# arduino_board_rev_1_4.net
KiCad netlist of a schematic drawn in EAGLE
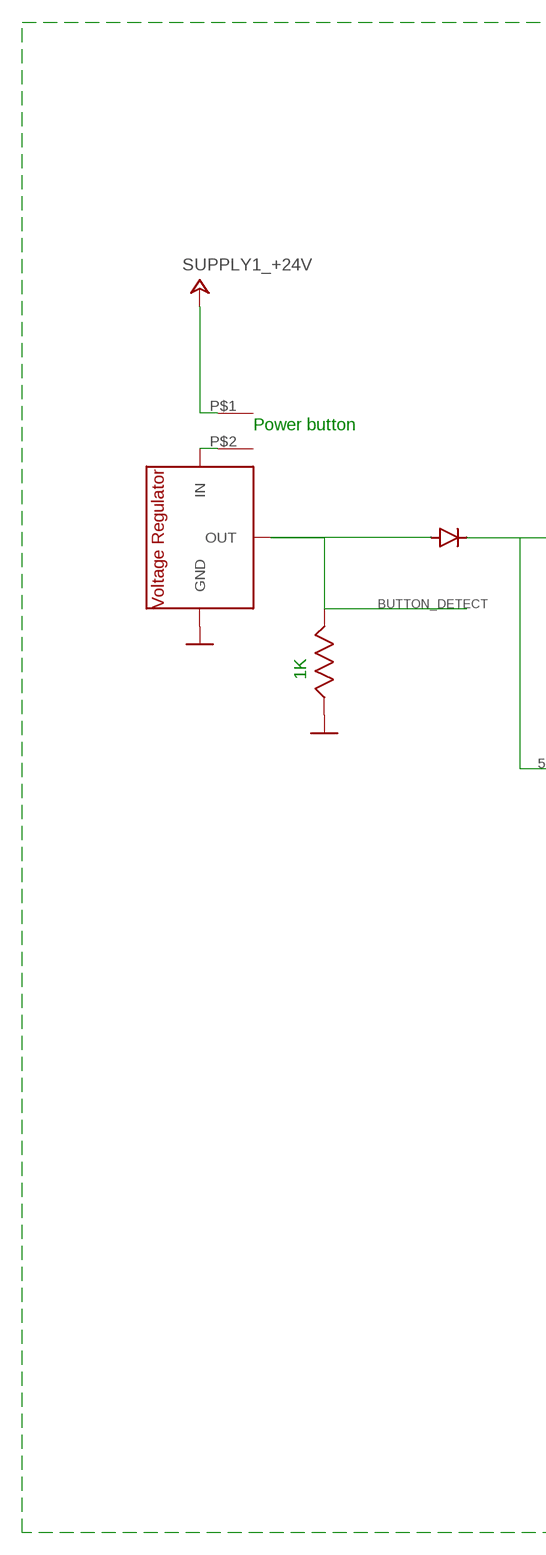
[diagram p0: schematic, sheet 1, part 1 of 2]
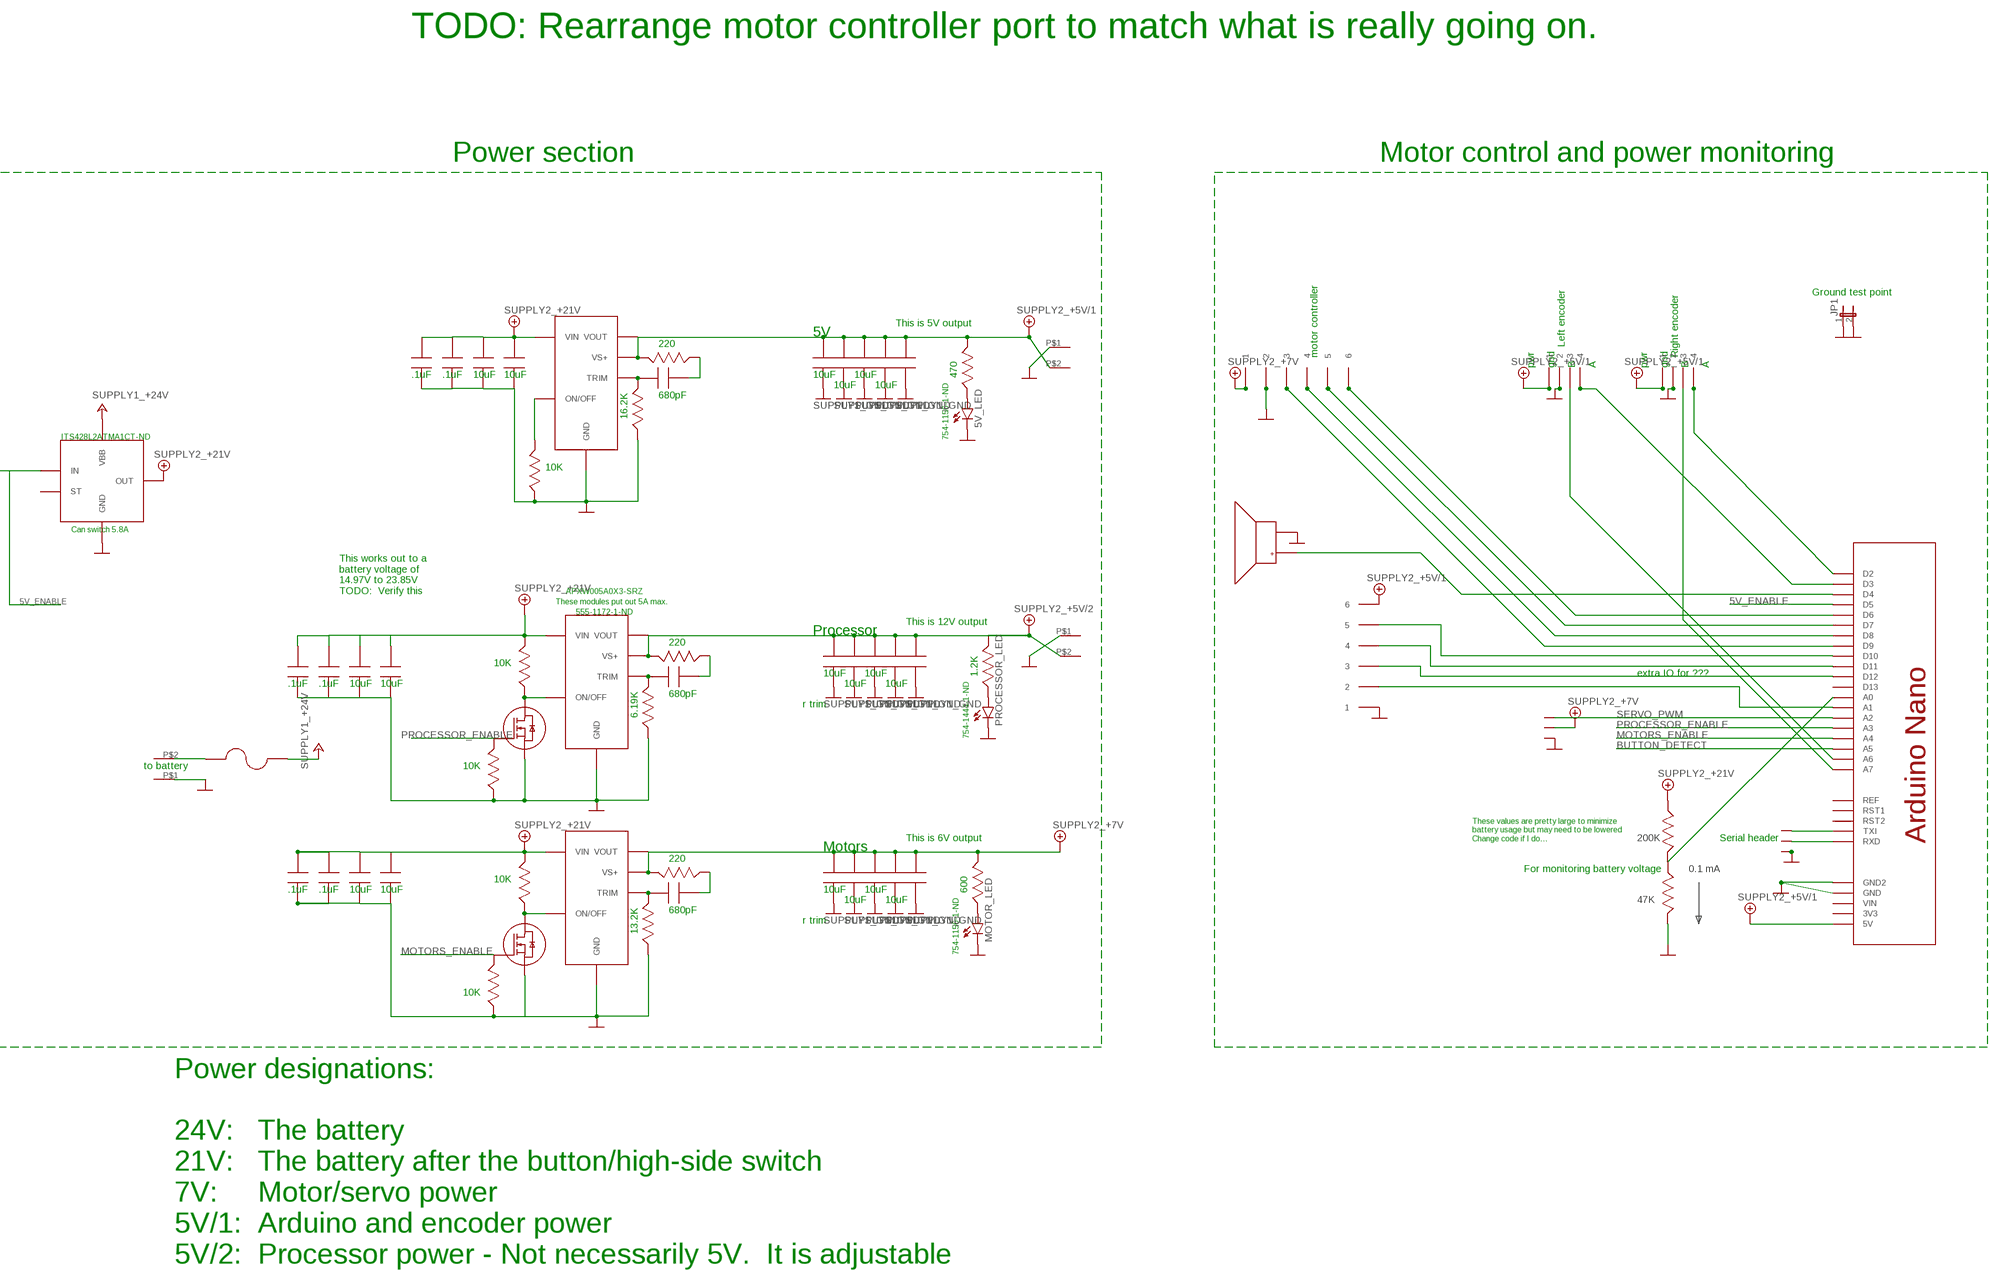
[diagram p1: schematic, sheet 1, part 2 of 2]

(export (version "E")
  (design (tool "Eeschema 10.0.6"))
  (components
    (comp (ref "5V_C_680PF")
      (value "JACK_CAPACITOR0805")
      (footprint "eagle-import:JACK_0805")
      (libsource (lib "eagle-import") (part "JACK_CAPACITOR0805"))
    )
    (comp (ref "5V_IN_CAP_1")
      (value "JACK_CAPACITOR")
      (footprint "eagle-import:JACK_1210")
      (libsource (lib "eagle-import") (part "JACK_CAPACITOR"))
    )
    (comp (ref "5V_IN_CAP_2")
      (value "JACK_CAPACITOR")
      (footprint "eagle-import:JACK_1210")
      (libsource (lib "eagle-import") (part "JACK_CAPACITOR"))
    )
    (comp (ref "5V_IN_CAP_3")
      (value "JACK_CAPACITOR")
      (footprint "eagle-import:JACK_1210")
      (libsource (lib "eagle-import") (part "JACK_CAPACITOR"))
    )
    (comp (ref "5V_IN_CAP_4")
      (value "JACK_CAPACITOR")
      (footprint "eagle-import:JACK_1210")
      (libsource (lib "eagle-import") (part "JACK_CAPACITOR"))
    )
    (comp (ref "5V_LED")
      (value "LED_LEDSML1206")
      (footprint "eagle-import:LED_SML1206")
      (libsource (lib "eagle-import") (part "LED_LEDSML1206"))
    )
    (comp (ref "5V_LED_R1")
      (value "JACK_RESISTOR0805")
      (footprint "eagle-import:JACK_0805")
      (libsource (lib "eagle-import") (part "JACK_RESISTOR0805"))
    )
    (comp (ref "5V_OUT_CAP_1")
      (value "JACK_CAPACITOR")
      (footprint "eagle-import:JACK_1210")
      (libsource (lib "eagle-import") (part "JACK_CAPACITOR"))
    )
    (comp (ref "5V_OUT_CAP_2")
      (value "JACK_CAPACITOR")
      (footprint "eagle-import:JACK_1210")
      (libsource (lib "eagle-import") (part "JACK_CAPACITOR"))
    )
    (comp (ref "5V_OUT_CAP_3")
      (value "JACK_CAPACITOR")
      (footprint "eagle-import:JACK_1210")
      (libsource (lib "eagle-import") (part "JACK_CAPACITOR"))
    )
    (comp (ref "5V_OUT_CAP_4")
      (value "JACK_CAPACITOR")
      (footprint "eagle-import:JACK_1210")
      (libsource (lib "eagle-import") (part "JACK_CAPACITOR"))
    )
    (comp (ref "5V_OUT_CAP_5")
      (value "JACK_CAPACITOR")
      (footprint "eagle-import:JACK_1210")
      (libsource (lib "eagle-import") (part "JACK_CAPACITOR"))
    )
    (comp (ref "5V_REGULATOR_PULLDOWN")
      (value "JACK_RESISTOR0805")
      (footprint "eagle-import:JACK_0805")
      (libsource (lib "eagle-import") (part "JACK_RESISTOR0805"))
    )
    (comp (ref "5V_R_220")
      (value "JACK_RESISTOR0805")
      (footprint "eagle-import:JACK_0805")
      (libsource (lib "eagle-import") (part "JACK_RESISTOR0805"))
    )
    (comp (ref "BATTERY_VOLTAGE_DIVIDER_HIGH")
      (value "JACK_RESISTOR0805")
      (footprint "eagle-import:JACK_0805")
      (libsource (lib "eagle-import") (part "JACK_RESISTOR0805"))
    )
    (comp (ref "BATTERY_VOLTAGE_DIVIDER_LOW")
      (value "JACK_RESISTOR0805")
      (footprint "eagle-import:JACK_0805")
      (libsource (lib "eagle-import") (part "JACK_RESISTOR0805"))
    )
    (comp (ref "BEEPER")
      (value "JACK_BEEPER")
      (footprint "eagle-import:JACK_BEEPER_433-1033-ND")
      (libsource (lib "eagle-import") (part "JACK_BEEPER"))
    )
    (comp (ref "DC2DC_PROCESSOR_")
      (value "JACK_DC_TO_DC_VARIABLE_555-1172-1-ND")
      (footprint "eagle-import:JACK_DC2DC_555-1172-1-ND")
      (libsource (lib "eagle-import") (part "JACK_DC_TO_DC_VARIABLE_555-1172-1-ND"))
    )
    (comp (ref "HIGH-SIDE_BLOCKING_DIODE")
      (value "JACK_DIODESOD-23/SC-76")
      (footprint "eagle-import:JACK_SOD-323_SC-76")
      (libsource (lib "eagle-import") (part "JACK_DIODESOD-23/SC-76"))
    )
    (comp (ref "HIGH-SIDE_SWITCH")
      (value "JACK_HIGH-SIDE_SWITCH_INFINEON_ITS428L2")
      (footprint "eagle-import:JACK_INFINEON_TO-252-5-11")
      (libsource (lib "eagle-import") (part "JACK_HIGH-SIDE_SWITCH_INFINEON_ITS428L2"))
    )
    (comp (ref "HIGH-SIDE_SWITCH_BUTTON_DIVIDER_LOW")
      (value "JACK_RESISTOR0805")
      (footprint "eagle-import:JACK_0805")
      (libsource (lib "eagle-import") (part "JACK_RESISTOR0805"))
    )
    (comp (ref "JP1")
      (value "JUMPER_JP1E")
      (footprint "eagle-import:JUMPER_JP1")
      (libsource (lib "eagle-import") (part "JUMPER_JP1E"))
    )
    (comp (ref "MOTOR.1UF")
      (value "JACK_CAPACITOR")
      (footprint "eagle-import:JACK_1210")
      (libsource (lib "eagle-import") (part "JACK_CAPACITOR"))
    )
    (comp (ref "MOTOR_C_680PF")
      (value "JACK_CAPACITOR0805")
      (footprint "eagle-import:JACK_0805")
      (libsource (lib "eagle-import") (part "JACK_CAPACITOR0805"))
    )
    (comp (ref "MOTOR_ENABLE_MOSFET")
      (value "JACK_MOSFET_N_CHANNELBSS138LCT-ND")
      (footprint "eagle-import:JACK_SOT23")
      (libsource (lib "eagle-import") (part "JACK_MOSFET_N_CHANNELBSS138LCT-ND"))
    )
    (comp (ref "MOTOR_IN.1UF")
      (value "JACK_CAPACITOR")
      (footprint "eagle-import:JACK_1210")
      (libsource (lib "eagle-import") (part "JACK_CAPACITOR"))
    )
    (comp (ref "MOTOR_IN.1UF1")
      (value "JACK_CAPACITOR")
      (footprint "eagle-import:JACK_1210")
      (libsource (lib "eagle-import") (part "JACK_CAPACITOR"))
    )
    (comp (ref "MOTOR_IN.1UF4")
      (value "JACK_CAPACITOR")
      (footprint "eagle-import:JACK_1210")
      (libsource (lib "eagle-import") (part "JACK_CAPACITOR"))
    )
    (comp (ref "MOTOR_IN10UF")
      (value "JACK_CAPACITOR")
      (footprint "eagle-import:JACK_1210")
      (libsource (lib "eagle-import") (part "JACK_CAPACITOR"))
    )
    (comp (ref "MOTOR_LED")
      (value "LED_LEDSML1206")
      (footprint "eagle-import:LED_SML1206")
      (libsource (lib "eagle-import") (part "LED_LEDSML1206"))
    )
    (comp (ref "MOTOR_LED_R")
      (value "JACK_RESISTOR0805")
      (footprint "eagle-import:JACK_0805")
      (libsource (lib "eagle-import") (part "JACK_RESISTOR0805"))
    )
    (comp (ref "MOTOR_MOSFET_PULLDOWN")
      (value "JACK_RESISTOR0805")
      (footprint "eagle-import:JACK_0805")
      (libsource (lib "eagle-import") (part "JACK_RESISTOR0805"))
    )
    (comp (ref "MOTOR_PULLUP")
      (value "JACK_RESISTOR0805")
      (footprint "eagle-import:JACK_0805")
      (libsource (lib "eagle-import") (part "JACK_RESISTOR0805"))
    )
    (comp (ref "MOTOR_R_220")
      (value "JACK_RESISTOR0805")
      (footprint "eagle-import:JACK_0805")
      (libsource (lib "eagle-import") (part "JACK_RESISTOR0805"))
    )
    (comp (ref "MOTOR_TRIM")
      (value "JACK_RESISTOR0805")
      (footprint "eagle-import:JACK_0805")
      (libsource (lib "eagle-import") (part "JACK_RESISTOR0805"))
    )
    (comp (ref "MOTOTR10UF")
      (value "JACK_CAPACITOR")
      (footprint "eagle-import:JACK_1210")
      (libsource (lib "eagle-import") (part "JACK_CAPACITOR"))
    )
    (comp (ref "MOTOTR10UF1")
      (value "JACK_CAPACITOR")
      (footprint "eagle-import:JACK_1210")
      (libsource (lib "eagle-import") (part "JACK_CAPACITOR"))
    )
    (comp (ref "MOTOTR10UF2")
      (value "JACK_CAPACITOR")
      (footprint "eagle-import:JACK_1210")
      (libsource (lib "eagle-import") (part "JACK_CAPACITOR"))
    )
    (comp (ref "MOTOTR10UF3")
      (value "JACK_CAPACITOR")
      (footprint "eagle-import:JACK_1210")
      (libsource (lib "eagle-import") (part "JACK_CAPACITOR"))
    )
    (comp (ref "PROC.1UF")
      (value "JACK_CAPACITOR")
      (footprint "eagle-import:JACK_1210")
      (libsource (lib "eagle-import") (part "JACK_CAPACITOR"))
    )
    (comp (ref "PROC10UF")
      (value "JACK_CAPACITOR")
      (footprint "eagle-import:JACK_1210")
      (libsource (lib "eagle-import") (part "JACK_CAPACITOR"))
    )
    (comp (ref "PROC10UF1")
      (value "JACK_CAPACITOR")
      (footprint "eagle-import:JACK_1210")
      (libsource (lib "eagle-import") (part "JACK_CAPACITOR"))
    )
    (comp (ref "PROC10UF2")
      (value "JACK_CAPACITOR")
      (footprint "eagle-import:JACK_1210")
      (libsource (lib "eagle-import") (part "JACK_CAPACITOR"))
    )
    (comp (ref "PROC10UF3")
      (value "JACK_CAPACITOR")
      (footprint "eagle-import:JACK_1210")
      (libsource (lib "eagle-import") (part "JACK_CAPACITOR"))
    )
    (comp (ref "PROCESSOR_C_680PF")
      (value "JACK_CAPACITOR0805")
      (footprint "eagle-import:JACK_0805")
      (libsource (lib "eagle-import") (part "JACK_CAPACITOR0805"))
    )
    (comp (ref "PROCESSOR_ENABLE_MOSFET")
      (value "JACK_MOSFET_N_CHANNELBSS138LCT-ND")
      (footprint "eagle-import:JACK_SOT23")
      (libsource (lib "eagle-import") (part "JACK_MOSFET_N_CHANNELBSS138LCT-ND"))
    )
    (comp (ref "PROCESSOR_LED")
      (value "LED_LEDSML1206")
      (footprint "eagle-import:LED_SML1206")
      (libsource (lib "eagle-import") (part "LED_LEDSML1206"))
    )
    (comp (ref "PROCESSOR_LED_R")
      (value "JACK_RESISTOR0805")
      (footprint "eagle-import:JACK_0805")
      (libsource (lib "eagle-import") (part "JACK_RESISTOR0805"))
    )
    (comp (ref "PROCESSOR_MOSFET_PULLDOWN")
      (value "JACK_RESISTOR0805")
      (footprint "eagle-import:JACK_0805")
      (libsource (lib "eagle-import") (part "JACK_RESISTOR0805"))
    )
    (comp (ref "PROCESSOR_PULLUP")
      (value "JACK_RESISTOR0805")
      (footprint "eagle-import:JACK_0805")
      (libsource (lib "eagle-import") (part "JACK_RESISTOR0805"))
    )
    (comp (ref "PROCESSOR_R_220")
      (value "JACK_RESISTOR0805")
      (footprint "eagle-import:JACK_0805")
      (libsource (lib "eagle-import") (part "JACK_RESISTOR0805"))
    )
    (comp (ref "PROC_IN10UF")
      (value "JACK_CAPACITOR")
      (footprint "eagle-import:JACK_1210")
      (libsource (lib "eagle-import") (part "JACK_CAPACITOR"))
    )
    (comp (ref "PROC_IN_.1UF")
      (value "JACK_CAPACITOR")
      (footprint "eagle-import:JACK_1210")
      (libsource (lib "eagle-import") (part "JACK_CAPACITOR"))
    )
    (comp (ref "PROC_IN_.1UF1")
      (value "JACK_CAPACITOR")
      (footprint "eagle-import:JACK_1210")
      (libsource (lib "eagle-import") (part "JACK_CAPACITOR"))
    )
    (comp (ref "PROC_IN_.1UF2")
      (value "JACK_CAPACITOR")
      (footprint "eagle-import:JACK_1210")
      (libsource (lib "eagle-import") (part "JACK_CAPACITOR"))
    )
    (comp (ref "RTRIM_5V")
      (value "JACK_RESISTOR0805")
      (footprint "eagle-import:JACK_0805")
      (libsource (lib "eagle-import") (part "JACK_RESISTOR0805"))
    )
    (comp (ref "RTRIM_PROCESSOR")
      (value "JACK_RESISTOR0805")
      (footprint "eagle-import:JACK_0805")
      (libsource (lib "eagle-import") (part "JACK_RESISTOR0805"))
    )
    (comp (ref "SERVO_HEADER")
      (value "JACK_CONNECTOR_3_PIN")
      (footprint "eagle-import:JACK_THREE_.1__HOLES")
      (libsource (lib "eagle-import") (part "JACK_CONNECTOR_3_PIN"))
    )
    (comp (ref "U$1")
      (value "JACK_SCREW_TERMINAL_2_CONDUCTORAMP-282837-2")
      (footprint "eagle-import:JACK_AMP-282837-2")
      (libsource (lib "eagle-import") (part "JACK_SCREW_TERMINAL_2_CONDUCTORAMP-282837-2"))
    )
    (comp (ref "U$2")
      (value "JACK_SCREW_TERMINAL_2_CONDUCTORAMP-282837-2")
      (footprint "eagle-import:JACK_AMP-282837-2")
      (libsource (lib "eagle-import") (part "JACK_SCREW_TERMINAL_2_CONDUCTORAMP-282837-2"))
    )
    (comp (ref "U$3")
      (value "JACK_CONNECTOR_6_PINJST_MAYBE")
      (footprint "eagle-import:JACK_JST_6_PIN_.1_")
      (libsource (lib "eagle-import") (part "JACK_CONNECTOR_6_PINJST_MAYBE"))
    )
    (comp (ref "U$4")
      (value "JACK_DC_TO_DC_VARIABLE_555-1172-1-ND")
      (footprint "eagle-import:JACK_DC2DC_555-1172-1-ND")
      (libsource (lib "eagle-import") (part "JACK_DC_TO_DC_VARIABLE_555-1172-1-ND"))
    )
    (comp (ref "U$5")
      (value "JACK_SCREW_TERMINAL_2_CONDUCTORAMP-282837-2")
      (footprint "eagle-import:JACK_AMP-282837-2")
      (libsource (lib "eagle-import") (part "JACK_SCREW_TERMINAL_2_CONDUCTORAMP-282837-2"))
    )
    (comp (ref "U$6")
      (value "JACK_SCREW_TERMINAL_2_CONDUCTORAMP-282837-2")
      (footprint "eagle-import:JACK_AMP-282837-2")
      (libsource (lib "eagle-import") (part "JACK_SCREW_TERMINAL_2_CONDUCTORAMP-282837-2"))
    )
    (comp (ref "U$7")
      (value "VOLTAGE_REGULATOR")
      (footprint "eagle-import:JACK_SOT23")
      (libsource (lib "eagle-import") (part "VOLTAGE_REGULATOR"))
    )
    (comp (ref "U$9")
      (value "JACK_CONNECTOR_6_PINJST_MAYBE")
      (footprint "eagle-import:JACK_JST_6_PIN_.1_")
      (libsource (lib "eagle-import") (part "JACK_CONNECTOR_6_PINJST_MAYBE"))
    )
    (comp (ref "U$10")
      (value "JACK_CONNECTOR_4_PIN")
      (footprint "eagle-import:JACK_JST_4_PIN_.1_")
      (libsource (lib "eagle-import") (part "JACK_CONNECTOR_4_PIN"))
    )
    (comp (ref "U$11")
      (value "JACK_FUSE_HOLDER_F065-ND")
      (footprint "eagle-import:JACK_FUSE_HOLDER_F064-ND")
      (libsource (lib "eagle-import") (part "JACK_FUSE_HOLDER_F065-ND"))
    )
    (comp (ref "U$12")
      (value "JACK_CONNECTOR_4_PIN")
      (footprint "eagle-import:JACK_JST_4_PIN_.1_")
      (libsource (lib "eagle-import") (part "JACK_CONNECTOR_4_PIN"))
    )
    (comp (ref "U$13")
      (value "JACK_CONNECTOR_3_PINMAYBE_JST")
      (footprint "eagle-import:JACK_JST_3_PIN_.1_")
      (libsource (lib "eagle-import") (part "JACK_CONNECTOR_3_PINMAYBE_JST"))
    )
    (comp (ref "U$14")
      (value "JACK_ARDUINO_NANO")
      (footprint "eagle-import:JACK_ARDUINO_NANO")
      (libsource (lib "eagle-import") (part "JACK_ARDUINO_NANO"))
    )
    (comp (ref "U$17")
      (value "JACK_DC_TO_DC_VARIABLE_555-1172-1-ND")
      (footprint "eagle-import:JACK_DC2DC_555-1172-1-ND")
      (libsource (lib "eagle-import") (part "JACK_DC_TO_DC_VARIABLE_555-1172-1-ND"))
    )
  )
  (nets
    (net (code "1") (name "/5V_ENABLE") (class "Default")
      (node (ref "HIGH-SIDE_BLOCKING_DIODE") (pin "C") (pinfunction "C_C") (pintype "bidirectional"))
      (node (ref "HIGH-SIDE_SWITCH") (pin "2") (pinfunction "IN_2") (pintype "bidirectional"))
      (node (ref "U$14") (pin "P$8") (pinfunction "D5_P$8") (pintype "bidirectional"))
    )
    (net (code "2") (name "/BUTTON_DETECT") (class "Default")
      (node (ref "HIGH-SIDE_BLOCKING_DIODE") (pin "A") (pinfunction "A_A") (pintype "bidirectional"))
      (node (ref "HIGH-SIDE_SWITCH_BUTTON_DIVIDER_LOW") (pin "P$3") (pinfunction "P$3_P$3") (pintype "bidirectional"))
      (node (ref "U$14") (pin "P$22") (pinfunction "A5_P$22") (pintype "bidirectional"))
      (node (ref "U$7") (pin "1") (pinfunction "OUT_1") (pintype "power_in"))
    )
    (net (code "3") (name "/MOTORS_ENABLE") (class "Default")
      (node (ref "MOTOR_ENABLE_MOSFET") (pin "1") (pinfunction "G_1") (pintype "bidirectional"))
      (node (ref "MOTOR_MOSFET_PULLDOWN") (pin "P$3") (pinfunction "P$3_P$3") (pintype "bidirectional"))
      (node (ref "U$14") (pin "P$23") (pinfunction "A4_P$23") (pintype "bidirectional"))
    )
    (net (code "4") (name "/PROCESSOR_ENABLE") (class "Default")
      (node (ref "PROCESSOR_ENABLE_MOSFET") (pin "1") (pinfunction "G_1") (pintype "bidirectional"))
      (node (ref "PROCESSOR_MOSFET_PULLDOWN") (pin "P$3") (pinfunction "P$3_P$3") (pintype "bidirectional"))
      (node (ref "U$14") (pin "P$24") (pinfunction "A3_P$24") (pintype "bidirectional"))
    )
    (net (code "5") (name "/SERVO_PWM") (class "Default")
      (node (ref "SERVO_HEADER") (pin "3") (pinfunction "3_3") (pintype "bidirectional"))
      (node (ref "U$14") (pin "P$25") (pinfunction "A2_P$25") (pintype "bidirectional"))
    )
    (net (code "6") (name "Net-(5V_C_680PF-1)") (class "Default")
      (node (ref "5V_C_680PF") (pin "P$2") (pinfunction "1_P$2") (pintype "bidirectional"))
      (node (ref "5V_R_220") (pin "P$2") (pinfunction "P$2_P$2") (pintype "bidirectional"))
    )
    (net (code "7") (name "Net-(5V_C_680PF-2)") (class "Default")
      (node (ref "5V_C_680PF") (pin "P$3") (pinfunction "2_P$3") (pintype "bidirectional"))
      (node (ref "RTRIM_5V") (pin "P$3") (pinfunction "P$3_P$3") (pintype "bidirectional"))
      (node (ref "U$4") (pin "TRIM") (pinfunction "TRIM_TRIM") (pintype "bidirectional"))
    )
    (net (code "8") (name "Net-(5V_LED-PadA)") (class "Default")
      (node (ref "5V_LED") (pin "A") (pinfunction "A_A") (pintype "passive"))
      (node (ref "5V_LED_R1") (pin "P$2") (pinfunction "P$2_P$2") (pintype "bidirectional"))
    )
    (net (code "9") (name "Net-(5V_REGULATOR_PULLDOWN-PadP$3)") (class "Default")
      (node (ref "5V_REGULATOR_PULLDOWN") (pin "P$3") (pinfunction "P$3_P$3") (pintype "bidirectional"))
      (node (ref "U$4") (pin "ON/OFF") (pinfunction "ON/OFF_ON/OFF") (pintype "bidirectional"))
    )
    (net (code "10") (name "Net-(MOTOR_C_680PF-1)") (class "Default")
      (node (ref "MOTOR_C_680PF") (pin "P$2") (pinfunction "1_P$2") (pintype "bidirectional"))
      (node (ref "MOTOR_R_220") (pin "P$2") (pinfunction "P$2_P$2") (pintype "bidirectional"))
    )
    (net (code "11") (name "Net-(MOTOR_C_680PF-2)") (class "Default")
      (node (ref "MOTOR_C_680PF") (pin "P$3") (pinfunction "2_P$3") (pintype "bidirectional"))
      (node (ref "MOTOR_TRIM") (pin "P$3") (pinfunction "P$3_P$3") (pintype "bidirectional"))
      (node (ref "U$17") (pin "TRIM") (pinfunction "TRIM_TRIM") (pintype "bidirectional"))
    )
    (net (code "12") (name "Net-(MOTOR_ENABLE_MOSFET-D)") (class "Default")
      (node (ref "MOTOR_ENABLE_MOSFET") (pin "3") (pinfunction "D_3") (pintype "bidirectional"))
      (node (ref "MOTOR_PULLUP") (pin "P$2") (pinfunction "P$2_P$2") (pintype "bidirectional"))
      (node (ref "U$17") (pin "ON/OFF") (pinfunction "ON/OFF_ON/OFF") (pintype "bidirectional"))
    )
    (net (code "13") (name "Net-(MOTOR_LED-PadA)") (class "Default")
      (node (ref "MOTOR_LED") (pin "A") (pinfunction "A_A") (pintype "passive"))
      (node (ref "MOTOR_LED_R") (pin "P$2") (pinfunction "P$2_P$2") (pintype "bidirectional"))
    )
    (net (code "14") (name "Net-(PROCESSOR_C_680PF-1)") (class "Default")
      (node (ref "PROCESSOR_C_680PF") (pin "P$2") (pinfunction "1_P$2") (pintype "bidirectional"))
      (node (ref "PROCESSOR_R_220") (pin "P$2") (pinfunction "P$2_P$2") (pintype "bidirectional"))
    )
    (net (code "15") (name "Net-(PROCESSOR_C_680PF-2)") (class "Default")
      (node (ref "DC2DC_PROCESSOR_") (pin "TRIM") (pinfunction "TRIM_TRIM") (pintype "bidirectional"))
      (node (ref "PROCESSOR_C_680PF") (pin "P$3") (pinfunction "2_P$3") (pintype "bidirectional"))
      (node (ref "RTRIM_PROCESSOR") (pin "P$3") (pinfunction "P$3_P$3") (pintype "bidirectional"))
    )
    (net (code "16") (name "Net-(PROCESSOR_ENABLE_MOSFET-D)") (class "Default")
      (node (ref "DC2DC_PROCESSOR_") (pin "ON/OFF") (pinfunction "ON/OFF_ON/OFF") (pintype "bidirectional"))
      (node (ref "PROCESSOR_ENABLE_MOSFET") (pin "3") (pinfunction "D_3") (pintype "bidirectional"))
      (node (ref "PROCESSOR_PULLUP") (pin "P$2") (pinfunction "P$2_P$2") (pintype "bidirectional"))
    )
    (net (code "17") (name "Net-(PROCESSOR_LED-PadA)") (class "Default")
      (node (ref "PROCESSOR_LED") (pin "A") (pinfunction "A_A") (pintype "passive"))
      (node (ref "PROCESSOR_LED_R") (pin "P$2") (pinfunction "P$2_P$2") (pintype "bidirectional"))
    )
    (net (code "18") (name "Net-(U$7-IN)") (class "Default")
      (node (ref "U$1") (pin "P$2") (pinfunction "P$2_P$2") (pintype "bidirectional"))
      (node (ref "U$7") (pin "2") (pinfunction "IN_2") (pintype "power_in"))
    )
    (net (code "19") (name "Net-(U$11-PadP$2)") (class "Default")
      (node (ref "U$11") (pin "P$2") (pinfunction "P$2_P$2") (pintype "bidirectional"))
      (node (ref "U$6") (pin "P$2") (pinfunction "P$2_P$2") (pintype "bidirectional"))
    )
    (net (code "20") (name "Net-(U$14-A0)") (class "Default")
      (node (ref "BATTERY_VOLTAGE_DIVIDER_HIGH") (pin "P$3") (pinfunction "P$3_P$3") (pintype "bidirectional"))
      (node (ref "BATTERY_VOLTAGE_DIVIDER_LOW") (pin "P$2") (pinfunction "P$2_P$2") (pintype "bidirectional"))
      (node (ref "U$14") (pin "P$27") (pinfunction "A0_P$27") (pintype "bidirectional"))
    )
    (net (code "21") (name "Net-(U$14-A1)") (class "Default")
      (node (ref "U$14") (pin "P$26") (pinfunction "A1_P$26") (pintype "bidirectional"))
      (node (ref "U$3") (pin "2") (pinfunction "2_2") (pintype "bidirectional"))
    )
    (net (code "22") (name "Net-(U$14-A6)") (class "Default")
      (node (ref "U$10") (pin "3") (pinfunction "3_3") (pintype "bidirectional"))
      (node (ref "U$14") (pin "P$21") (pinfunction "A6_P$21") (pintype "bidirectional"))
    )
    (net (code "23") (name "Net-(U$14-A7)") (class "Default")
      (node (ref "U$12") (pin "3") (pinfunction "3_3") (pintype "bidirectional"))
      (node (ref "U$14") (pin "P$20") (pinfunction "A7_P$20") (pintype "bidirectional"))
    )
    (net (code "24") (name "Net-(U$14-D2)") (class "Default")
      (node (ref "U$12") (pin "4") (pinfunction "4_4") (pintype "bidirectional"))
      (node (ref "U$14") (pin "P$11") (pinfunction "D2_P$11") (pintype "bidirectional"))
    )
    (net (code "25") (name "Net-(U$14-D3)") (class "Default")
      (node (ref "U$10") (pin "4") (pinfunction "4_4") (pintype "bidirectional"))
      (node (ref "U$14") (pin "P$10") (pinfunction "D3_P$10") (pintype "bidirectional"))
    )
    (net (code "26") (name "Net-(U$14-D4)") (class "Default")
      (node (ref "BEEPER") (pin "+") (pinfunction "+_+") (pintype "bidirectional"))
      (node (ref "U$14") (pin "P$9") (pinfunction "D4_P$9") (pintype "bidirectional"))
    )
    (net (code "27") (name "Net-(U$14-D6)") (class "Default")
      (node (ref "U$14") (pin "P$7") (pinfunction "D6_P$7") (pintype "bidirectional"))
      (node (ref "U$9") (pin "6") (pinfunction "6_6") (pintype "bidirectional"))
    )
    (net (code "28") (name "Net-(U$14-D7)") (class "Default")
      (node (ref "U$14") (pin "P$6") (pinfunction "D7_P$6") (pintype "bidirectional"))
      (node (ref "U$9") (pin "5") (pinfunction "5_5") (pintype "bidirectional"))
    )
    (net (code "29") (name "Net-(U$14-D8)") (class "Default")
      (node (ref "U$14") (pin "P$5") (pinfunction "D8_P$5") (pintype "bidirectional"))
      (node (ref "U$9") (pin "4") (pinfunction "4_4") (pintype "bidirectional"))
    )
    (net (code "30") (name "Net-(U$14-D9)") (class "Default")
      (node (ref "U$14") (pin "P$4") (pinfunction "D9_P$4") (pintype "bidirectional"))
      (node (ref "U$9") (pin "3") (pinfunction "3_3") (pintype "bidirectional"))
    )
    (net (code "31") (name "Net-(U$14-D10)") (class "Default")
      (node (ref "U$14") (pin "P$3") (pinfunction "D10_P$3") (pintype "bidirectional"))
      (node (ref "U$3") (pin "5") (pinfunction "5_5") (pintype "bidirectional"))
    )
    (net (code "32") (name "Net-(U$14-D11)") (class "Default")
      (node (ref "U$14") (pin "P$2") (pinfunction "D11_P$2") (pintype "bidirectional"))
      (node (ref "U$3") (pin "4") (pinfunction "4_4") (pintype "bidirectional"))
    )
    (net (code "33") (name "Net-(U$14-D12)") (class "Default")
      (node (ref "U$14") (pin "P$1") (pinfunction "D12_P$1") (pintype "bidirectional"))
      (node (ref "U$3") (pin "3") (pinfunction "3_3") (pintype "bidirectional"))
    )
    (net (code "34") (name "Net-(U$14-RXD)") (class "Default")
      (node (ref "U$13") (pin "2") (pinfunction "2_2") (pintype "bidirectional"))
      (node (ref "U$14") (pin "P$14") (pinfunction "RXD_P$14") (pintype "bidirectional"))
    )
    (net (code "35") (name "Net-(U$14-TXI)") (class "Default")
      (node (ref "U$13") (pin "3") (pinfunction "3_3") (pintype "bidirectional"))
      (node (ref "U$14") (pin "P$15") (pinfunction "TXI_P$15") (pintype "bidirectional"))
    )
    (net (code "36") (name "SUPPLY1_+24V") (class "Default")
      (node (ref "HIGH-SIDE_SWITCH") (pin "TAB") (pinfunction "VBB_TAB") (pintype "bidirectional"))
      (node (ref "U$1") (pin "P$1") (pinfunction "P$1_P$1") (pintype "bidirectional"))
      (node (ref "U$11") (pin "P$1") (pinfunction "P$1_P$1") (pintype "bidirectional"))
    )
    (net (code "37") (name "SUPPLY1_GND") (class "Default")
      (node (ref "5V_IN_CAP_1") (pin "1") (pinfunction "1_1") (pintype "bidirectional"))
      (node (ref "5V_IN_CAP_2") (pin "1") (pinfunction "1_1") (pintype "bidirectional"))
      (node (ref "5V_IN_CAP_3") (pin "1") (pinfunction "1_1") (pintype "bidirectional"))
      (node (ref "5V_IN_CAP_4") (pin "1") (pinfunction "1_1") (pintype "bidirectional"))
      (node (ref "5V_LED") (pin "C") (pinfunction "C_C") (pintype "passive"))
      (node (ref "5V_OUT_CAP_1") (pin "1") (pinfunction "1_1") (pintype "bidirectional"))
      (node (ref "5V_OUT_CAP_2") (pin "1") (pinfunction "1_1") (pintype "bidirectional"))
      (node (ref "5V_OUT_CAP_3") (pin "1") (pinfunction "1_1") (pintype "bidirectional"))
      (node (ref "5V_OUT_CAP_4") (pin "1") (pinfunction "1_1") (pintype "bidirectional"))
      (node (ref "5V_OUT_CAP_5") (pin "1") (pinfunction "1_1") (pintype "bidirectional"))
      (node (ref "5V_REGULATOR_PULLDOWN") (pin "P$2") (pinfunction "P$2_P$2") (pintype "bidirectional"))
      (node (ref "BATTERY_VOLTAGE_DIVIDER_LOW") (pin "P$3") (pinfunction "P$3_P$3") (pintype "bidirectional"))
      (node (ref "BEEPER") (pin "-") (pinfunction "-_-") (pintype "bidirectional"))
      (node (ref "DC2DC_PROCESSOR_") (pin "GND") (pinfunction "GND_GND") (pintype "bidirectional"))
      (node (ref "HIGH-SIDE_SWITCH") (pin "1") (pinfunction "GND_1") (pintype "bidirectional"))
      (node (ref "HIGH-SIDE_SWITCH_BUTTON_DIVIDER_LOW") (pin "P$2") (pinfunction "P$2_P$2") (pintype "bidirectional"))
      (node (ref "JP1") (pin "1") (pinfunction "1_1") (pintype "passive"))
      (node (ref "JP1") (pin "2") (pinfunction "2_2") (pintype "passive"))
      (node (ref "MOTOR.1UF") (pin "1") (pinfunction "1_1") (pintype "bidirectional"))
      (node (ref "MOTOR_ENABLE_MOSFET") (pin "2") (pinfunction "S_2") (pintype "bidirectional"))
      (node (ref "MOTOR_IN.1UF") (pin "1") (pinfunction "1_1") (pintype "bidirectional"))
      (node (ref "MOTOR_IN.1UF1") (pin "1") (pinfunction "1_1") (pintype "bidirectional"))
      (node (ref "MOTOR_IN.1UF4") (pin "1") (pinfunction "1_1") (pintype "bidirectional"))
      (node (ref "MOTOR_IN10UF") (pin "1") (pinfunction "1_1") (pintype "bidirectional"))
      (node (ref "MOTOR_LED") (pin "C") (pinfunction "C_C") (pintype "passive"))
      (node (ref "MOTOR_MOSFET_PULLDOWN") (pin "P$2") (pinfunction "P$2_P$2") (pintype "bidirectional"))
      (node (ref "MOTOR_TRIM") (pin "P$2") (pinfunction "P$2_P$2") (pintype "bidirectional"))
      (node (ref "MOTOTR10UF") (pin "1") (pinfunction "1_1") (pintype "bidirectional"))
      (node (ref "MOTOTR10UF1") (pin "1") (pinfunction "1_1") (pintype "bidirectional"))
      (node (ref "MOTOTR10UF2") (pin "1") (pinfunction "1_1") (pintype "bidirectional"))
      (node (ref "MOTOTR10UF3") (pin "1") (pinfunction "1_1") (pintype "bidirectional"))
      (node (ref "PROC.1UF") (pin "1") (pinfunction "1_1") (pintype "bidirectional"))
      (node (ref "PROC10UF") (pin "1") (pinfunction "1_1") (pintype "bidirectional"))
      (node (ref "PROC10UF1") (pin "1") (pinfunction "1_1") (pintype "bidirectional"))
      (node (ref "PROC10UF2") (pin "1") (pinfunction "1_1") (pintype "bidirectional"))
      (node (ref "PROC10UF3") (pin "1") (pinfunction "1_1") (pintype "bidirectional"))
      (node (ref "PROCESSOR_ENABLE_MOSFET") (pin "2") (pinfunction "S_2") (pintype "bidirectional"))
      (node (ref "PROCESSOR_LED") (pin "C") (pinfunction "C_C") (pintype "passive"))
      (node (ref "PROCESSOR_MOSFET_PULLDOWN") (pin "P$2") (pinfunction "P$2_P$2") (pintype "bidirectional"))
      (node (ref "PROC_IN10UF") (pin "1") (pinfunction "1_1") (pintype "bidirectional"))
      (node (ref "PROC_IN_.1UF") (pin "1") (pinfunction "1_1") (pintype "bidirectional"))
      (node (ref "PROC_IN_.1UF1") (pin "1") (pinfunction "1_1") (pintype "bidirectional"))
      (node (ref "PROC_IN_.1UF2") (pin "1") (pinfunction "1_1") (pintype "bidirectional"))
      (node (ref "RTRIM_5V") (pin "P$2") (pinfunction "P$2_P$2") (pintype "bidirectional"))
      (node (ref "RTRIM_PROCESSOR") (pin "P$2") (pinfunction "P$2_P$2") (pintype "bidirectional"))
      (node (ref "SERVO_HEADER") (pin "1") (pinfunction "1_1") (pintype "bidirectional"))
      (node (ref "U$10") (pin "2") (pinfunction "2_2") (pintype "bidirectional"))
      (node (ref "U$12") (pin "2") (pinfunction "2_2") (pintype "bidirectional"))
      (node (ref "U$13") (pin "1") (pinfunction "1_1") (pintype "bidirectional"))
      (node (ref "U$14") (pin "P$12") (pinfunction "GND_P$12") (pintype "bidirectional"))
      (node (ref "U$14") (pin "P$17") (pinfunction "GND2_P$17") (pintype "bidirectional"))
      (node (ref "U$17") (pin "GND") (pinfunction "GND_GND") (pintype "bidirectional"))
      (node (ref "U$2") (pin "P$1") (pinfunction "P$1_P$1") (pintype "bidirectional"))
      (node (ref "U$3") (pin "1") (pinfunction "1_1") (pintype "bidirectional"))
      (node (ref "U$4") (pin "GND") (pinfunction "GND_GND") (pintype "bidirectional"))
      (node (ref "U$5") (pin "P$1") (pinfunction "P$1_P$1") (pintype "bidirectional"))
      (node (ref "U$6") (pin "P$1") (pinfunction "P$1_P$1") (pintype "bidirectional"))
      (node (ref "U$7") (pin "3") (pinfunction "GND_3") (pintype "power_in"))
      (node (ref "U$9") (pin "2") (pinfunction "2_2") (pintype "bidirectional"))
    )
    (net (code "38") (name "SUPPLY2_+5V{slash}1") (class "Default")
      (node (ref "5V_LED_R1") (pin "P$3") (pinfunction "P$3_P$3") (pintype "bidirectional"))
      (node (ref "5V_OUT_CAP_1") (pin "2") (pinfunction "2_2") (pintype "bidirectional"))
      (node (ref "5V_OUT_CAP_2") (pin "2") (pinfunction "2_2") (pintype "bidirectional"))
      (node (ref "5V_OUT_CAP_3") (pin "2") (pinfunction "2_2") (pintype "bidirectional"))
      (node (ref "5V_OUT_CAP_4") (pin "2") (pinfunction "2_2") (pintype "bidirectional"))
      (node (ref "5V_OUT_CAP_5") (pin "2") (pinfunction "2_2") (pintype "bidirectional"))
      (node (ref "5V_R_220") (pin "P$3") (pinfunction "P$3_P$3") (pintype "bidirectional"))
      (node (ref "U$10") (pin "1") (pinfunction "1_1") (pintype "bidirectional"))
      (node (ref "U$12") (pin "1") (pinfunction "1_1") (pintype "bidirectional"))
      (node (ref "U$14") (pin "P$19") (pinfunction "5V_P$19") (pintype "bidirectional"))
      (node (ref "U$2") (pin "P$2") (pinfunction "P$2_P$2") (pintype "bidirectional"))
      (node (ref "U$3") (pin "6") (pinfunction "6_6") (pintype "bidirectional"))
      (node (ref "U$4") (pin "VOUT") (pinfunction "VOUT_VOUT") (pintype "bidirectional"))
      (node (ref "U$4") (pin "VS+") (pinfunction "VS+_VS+") (pintype "bidirectional"))
    )
    (net (code "39") (name "SUPPLY2_+5V{slash}2") (class "Default")
      (node (ref "DC2DC_PROCESSOR_") (pin "VOUT") (pinfunction "VOUT_VOUT") (pintype "bidirectional"))
      (node (ref "DC2DC_PROCESSOR_") (pin "VS+") (pinfunction "VS+_VS+") (pintype "bidirectional"))
      (node (ref "PROC.1UF") (pin "2") (pinfunction "2_2") (pintype "bidirectional"))
      (node (ref "PROC10UF") (pin "2") (pinfunction "2_2") (pintype "bidirectional"))
      (node (ref "PROC10UF1") (pin "2") (pinfunction "2_2") (pintype "bidirectional"))
      (node (ref "PROC10UF2") (pin "2") (pinfunction "2_2") (pintype "bidirectional"))
      (node (ref "PROC10UF3") (pin "2") (pinfunction "2_2") (pintype "bidirectional"))
      (node (ref "PROCESSOR_LED_R") (pin "P$3") (pinfunction "P$3_P$3") (pintype "bidirectional"))
      (node (ref "PROCESSOR_R_220") (pin "P$3") (pinfunction "P$3_P$3") (pintype "bidirectional"))
      (node (ref "U$5") (pin "P$2") (pinfunction "P$2_P$2") (pintype "bidirectional"))
    )
    (net (code "40") (name "SUPPLY2_+7V") (class "Default")
      (node (ref "MOTOR.1UF") (pin "2") (pinfunction "2_2") (pintype "bidirectional"))
      (node (ref "MOTOR_LED_R") (pin "P$3") (pinfunction "P$3_P$3") (pintype "bidirectional"))
      (node (ref "MOTOR_R_220") (pin "P$3") (pinfunction "P$3_P$3") (pintype "bidirectional"))
      (node (ref "MOTOTR10UF") (pin "2") (pinfunction "2_2") (pintype "bidirectional"))
      (node (ref "MOTOTR10UF1") (pin "2") (pinfunction "2_2") (pintype "bidirectional"))
      (node (ref "MOTOTR10UF2") (pin "2") (pinfunction "2_2") (pintype "bidirectional"))
      (node (ref "MOTOTR10UF3") (pin "2") (pinfunction "2_2") (pintype "bidirectional"))
      (node (ref "SERVO_HEADER") (pin "2") (pinfunction "2_2") (pintype "bidirectional"))
      (node (ref "U$17") (pin "VOUT") (pinfunction "VOUT_VOUT") (pintype "bidirectional"))
      (node (ref "U$17") (pin "VS+") (pinfunction "VS+_VS+") (pintype "bidirectional"))
      (node (ref "U$9") (pin "1") (pinfunction "1_1") (pintype "bidirectional"))
    )
    (net (code "41") (name "SUPPLY2_+21V") (class "Default")
      (node (ref "5V_IN_CAP_1") (pin "2") (pinfunction "2_2") (pintype "bidirectional"))
      (node (ref "5V_IN_CAP_2") (pin "2") (pinfunction "2_2") (pintype "bidirectional"))
      (node (ref "5V_IN_CAP_3") (pin "2") (pinfunction "2_2") (pintype "bidirectional"))
      (node (ref "5V_IN_CAP_4") (pin "2") (pinfunction "2_2") (pintype "bidirectional"))
      (node (ref "BATTERY_VOLTAGE_DIVIDER_HIGH") (pin "P$2") (pinfunction "P$2_P$2") (pintype "bidirectional"))
      (node (ref "DC2DC_PROCESSOR_") (pin "VIN") (pinfunction "VIN_VIN") (pintype "bidirectional"))
      (node (ref "HIGH-SIDE_SWITCH") (pin "5") (pinfunction "OUT_5") (pintype "bidirectional"))
      (node (ref "MOTOR_IN.1UF") (pin "2") (pinfunction "2_2") (pintype "bidirectional"))
      (node (ref "MOTOR_IN.1UF1") (pin "2") (pinfunction "2_2") (pintype "bidirectional"))
      (node (ref "MOTOR_IN.1UF4") (pin "2") (pinfunction "2_2") (pintype "bidirectional"))
      (node (ref "MOTOR_IN10UF") (pin "2") (pinfunction "2_2") (pintype "bidirectional"))
      (node (ref "MOTOR_PULLUP") (pin "P$3") (pinfunction "P$3_P$3") (pintype "bidirectional"))
      (node (ref "PROCESSOR_PULLUP") (pin "P$3") (pinfunction "P$3_P$3") (pintype "bidirectional"))
      (node (ref "PROC_IN10UF") (pin "2") (pinfunction "2_2") (pintype "bidirectional"))
      (node (ref "PROC_IN_.1UF") (pin "2") (pinfunction "2_2") (pintype "bidirectional"))
      (node (ref "PROC_IN_.1UF1") (pin "2") (pinfunction "2_2") (pintype "bidirectional"))
      (node (ref "PROC_IN_.1UF2") (pin "2") (pinfunction "2_2") (pintype "bidirectional"))
      (node (ref "U$17") (pin "VIN") (pinfunction "VIN_VIN") (pintype "bidirectional"))
      (node (ref "U$4") (pin "VIN") (pinfunction "VIN_VIN") (pintype "bidirectional"))
    )
    (net (code "42") (name "unconnected-(HIGH-SIDE_SWITCH-ST-Pad4)") (class "Default")
      (node (ref "HIGH-SIDE_SWITCH") (pin "4") (pinfunction "ST_4") (pintype "bidirectional"))
    )
    (net (code "43") (name "unconnected-(U$14-3V3-PadP$29)") (class "Default")
      (node (ref "U$14") (pin "P$29") (pinfunction "3V3_P$29") (pintype "bidirectional"))
    )
    (net (code "44") (name "unconnected-(U$14-D13-PadP$30)") (class "Default")
      (node (ref "U$14") (pin "P$30") (pinfunction "D13_P$30") (pintype "bidirectional"))
    )
    (net (code "45") (name "unconnected-(U$14-REF-PadP$28)") (class "Default")
      (node (ref "U$14") (pin "P$28") (pinfunction "REF_P$28") (pintype "bidirectional"))
    )
    (net (code "46") (name "unconnected-(U$14-RST1-PadP$13)") (class "Default")
      (node (ref "U$14") (pin "P$13") (pinfunction "RST1_P$13") (pintype "bidirectional"))
    )
    (net (code "47") (name "unconnected-(U$14-RST2-PadP$18)") (class "Default")
      (node (ref "U$14") (pin "P$18") (pinfunction "RST2_P$18") (pintype "bidirectional"))
    )
    (net (code "48") (name "unconnected-(U$14-VIN-PadP$16)") (class "Default")
      (node (ref "U$14") (pin "P$16") (pinfunction "VIN_P$16") (pintype "bidirectional"))
    )
  )
)
